# OpenMV-2L.net
KiCad netlist of a schematic drawn in EAGLE
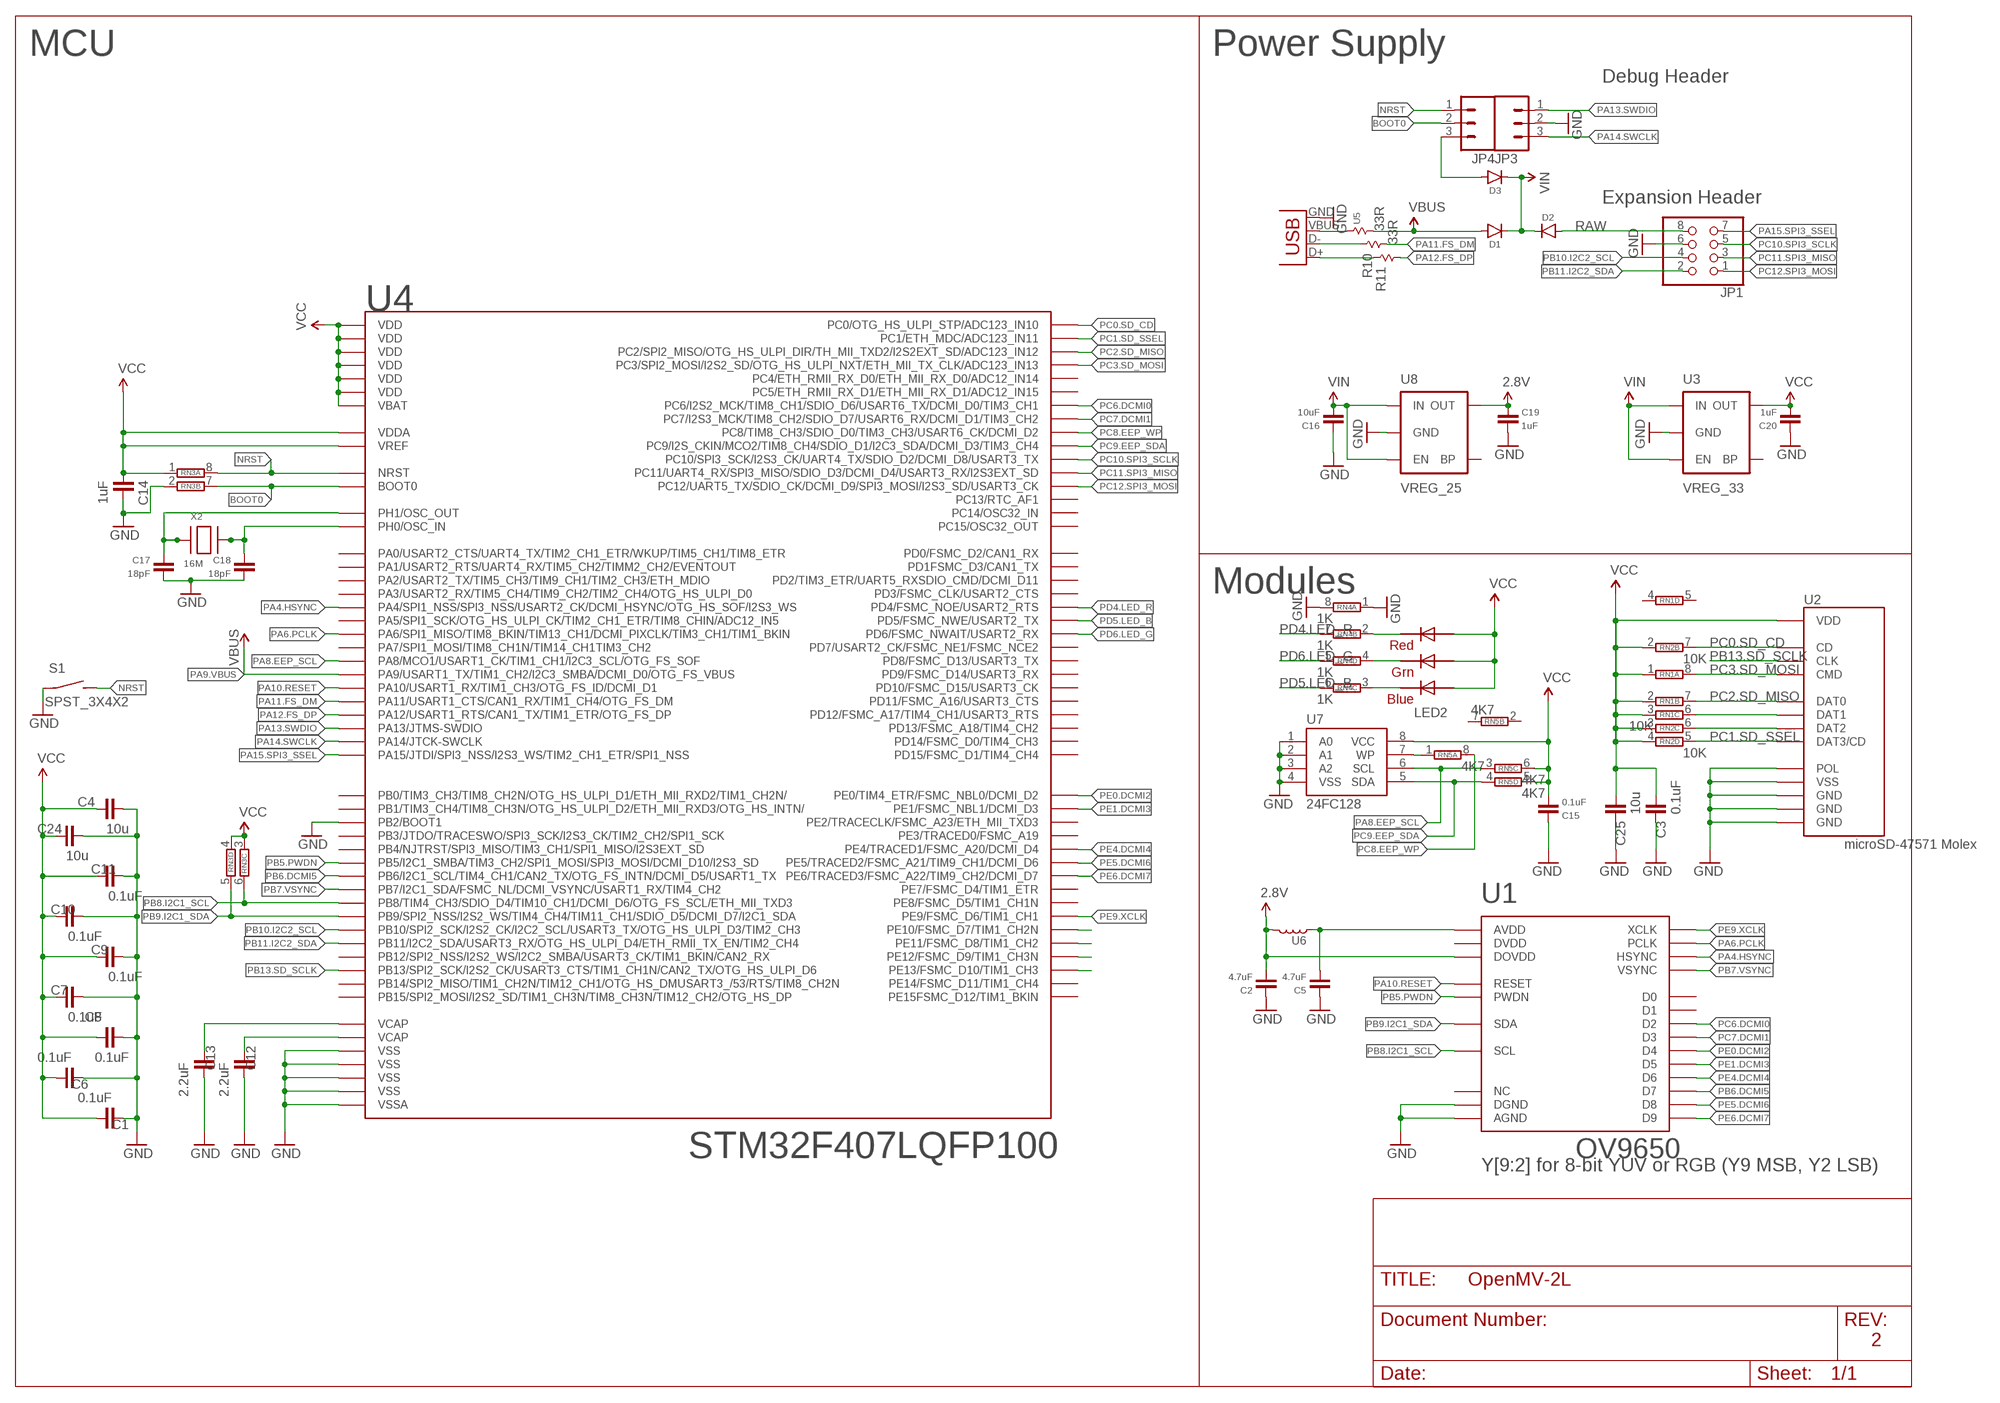
[diagram p0: schematic, sheet 1]

(export (version "E")
  (design (tool "Eeschema 10.0.6"))
  (components
    (comp (ref "C1")
      (value "0.1uF")
      (footprint "eagle-import:0402")
      (libsource (lib "eagle-import") (part "CAP-0402"))
    )
    (comp (ref "C2")
      (value "4.7uF")
      (footprint "eagle-import:0603")
      (libsource (lib "eagle-import") (part "CAP-0603"))
    )
    (comp (ref "C3")
      (value "0.1uF")
      (footprint "eagle-import:0402")
      (libsource (lib "eagle-import") (part "CAP-0402"))
    )
    (comp (ref "C4")
      (value "10u")
      (footprint "eagle-import:0805")
      (libsource (lib "eagle-import") (part "CAP-0805"))
    )
    (comp (ref "C5")
      (value "4.7uF")
      (footprint "eagle-import:0603")
      (libsource (lib "eagle-import") (part "CAP-0603"))
    )
    (comp (ref "C6")
      (value "0.1uF")
      (footprint "eagle-import:0402")
      (libsource (lib "eagle-import") (part "CAP-0402"))
    )
    (comp (ref "C7")
      (value "0.1uF")
      (footprint "eagle-import:0402")
      (libsource (lib "eagle-import") (part "CAP-0402"))
    )
    (comp (ref "C8")
      (value "0.1uF")
      (footprint "eagle-import:0402")
      (libsource (lib "eagle-import") (part "CAP-0402"))
    )
    (comp (ref "C9")
      (value "0.1uF")
      (footprint "eagle-import:0402")
      (libsource (lib "eagle-import") (part "CAP-0402"))
    )
    (comp (ref "C10")
      (value "0.1uF")
      (footprint "eagle-import:0402")
      (libsource (lib "eagle-import") (part "CAP-0402"))
    )
    (comp (ref "C11")
      (value "0.1uF")
      (footprint "eagle-import:0402")
      (libsource (lib "eagle-import") (part "CAP-0402"))
    )
    (comp (ref "C12")
      (value "2.2uF")
      (footprint "eagle-import:0402")
      (libsource (lib "eagle-import") (part "CAP-0402"))
    )
    (comp (ref "C13")
      (value "2.2uF")
      (footprint "eagle-import:0402")
      (libsource (lib "eagle-import") (part "CAP-0402"))
    )
    (comp (ref "C14")
      (value "1uF")
      (footprint "eagle-import:0402")
      (libsource (lib "eagle-import") (part "CAP-0402"))
    )
    (comp (ref "C15")
      (value "0.1uF")
      (footprint "eagle-import:0603")
      (libsource (lib "eagle-import") (part "CAP-0603"))
    )
    (comp (ref "C16")
      (value "10uF")
      (footprint "eagle-import:0805")
      (libsource (lib "eagle-import") (part "CAP-0805"))
    )
    (comp (ref "C17")
      (value "18pF")
      (footprint "eagle-import:0402")
      (libsource (lib "eagle-import") (part "CAP-0402"))
    )
    (comp (ref "C18")
      (value "18pF")
      (footprint "eagle-import:0402")
      (libsource (lib "eagle-import") (part "CAP-0402"))
    )
    (comp (ref "C19")
      (value "1uF")
      (footprint "eagle-import:0603")
      (libsource (lib "eagle-import") (part "CAP-0603"))
    )
    (comp (ref "C20")
      (value "1uF")
      (footprint "eagle-import:0603")
      (libsource (lib "eagle-import") (part "CAP-0603"))
    )
    (comp (ref "C24")
      (value "10u")
      (footprint "eagle-import:0805")
      (libsource (lib "eagle-import") (part "CAP-0805"))
    )
    (comp (ref "C25")
      (value "10u")
      (footprint "eagle-import:0805")
      (libsource (lib "eagle-import") (part "CAP-0805"))
    )
    (comp (ref "D1")
      (value "DIODE-SOD-323")
      (footprint "eagle-import:SOD-323")
      (libsource (lib "eagle-import") (part "DIODE-SOD-323"))
    )
    (comp (ref "D2")
      (value "DIODE-SOD-323")
      (footprint "eagle-import:SOD-323")
      (libsource (lib "eagle-import") (part "DIODE-SOD-323"))
    )
    (comp (ref "D3")
      (value "DIODE-SOD-323")
      (footprint "eagle-import:SOD-323")
      (libsource (lib "eagle-import") (part "DIODE-SOD-323"))
    )
    (comp (ref "JP1")
      (value "PINHD-2X4")
      (footprint "eagle-import:2X04")
      (libsource (lib "eagle-import") (part "PINHD-2X4"))
    )
    (comp (ref "JP3")
      (value "M03PTH")
      (footprint "eagle-import:1X03")
      (libsource (lib "eagle-import") (part "M03PTH"))
    )
    (comp (ref "JP4")
      (value "M03PTH")
      (footprint "eagle-import:1X03")
      (libsource (lib "eagle-import") (part "M03PTH"))
    )
    (comp (ref "LED2")
      (value "RGBLED5050")
      (footprint "eagle-import:RGBLED5050")
      (libsource (lib "eagle-import") (part "RGBLED5050"))
    )
    (comp (ref "R10")
      (value "33R")
      (footprint "eagle-import:0402")
      (libsource (lib "eagle-import") (part "RESISTOR-0402"))
    )
    (comp (ref "R11")
      (value "33R")
      (footprint "eagle-import:0402")
      (libsource (lib "eagle-import") (part "RESISTOR-0402"))
    )
    (comp (ref "RN1")
      (value "4R-NCAT16")
      (footprint "eagle-import:CAT16")
      (fields (field (name "OC_FARNELL") "unknown") (field (name "OC_NEWARK") "unknown"))
      (libsource (lib "eagle-import") (part "4R-NCAT16"))
    )
    (comp (ref "RN2")
      (value "10K")
      (footprint "eagle-import:CAT16")
      (fields (field (name "OC_FARNELL") "unknown") (field (name "OC_NEWARK") "unknown"))
      (libsource (lib "eagle-import") (part "4R-NCAT16"))
    )
    (comp (ref "RN3")
      (value "4R-NCAT16")
      (footprint "eagle-import:CAT16")
      (libsource (lib "eagle-import") (part "4R-NCAT16"))
    )
    (comp (ref "RN4")
      (value "1K")
      (footprint "eagle-import:CAT16")
      (fields (field (name "OC_FARNELL") "unknown") (field (name "OC_NEWARK") "unknown"))
      (libsource (lib "eagle-import") (part "4R-NCAT16"))
    )
    (comp (ref "RN5")
      (value "4K7")
      (footprint "eagle-import:CAT16")
      (fields (field (name "OC_FARNELL") "unknown") (field (name "OC_NEWARK") "unknown"))
      (libsource (lib "eagle-import") (part "4R-NCAT16"))
    )
    (comp (ref "S1")
      (value "SPST_3X4X2")
      (footprint "eagle-import:3X4X2TACT")
      (libsource (lib "eagle-import") (part "SPST_3X4X2"))
    )
    (comp (ref "U1")
      (value "OV9650")
      (footprint "eagle-import:OV9650")
      (libsource (lib "eagle-import") (part "OV9650"))
    )
    (comp (ref "U2")
      (value "microSD-47571 Molex")
      (footprint "eagle-import:USD-47571")
      (libsource (lib "eagle-import") (part "USD-47571"))
    )
    (comp (ref "U3")
      (value "VREG_33")
      (footprint "eagle-import:SOT23-5")
      (libsource (lib "eagle-import") (part "V_REG_LDOSMD"))
    )
    (comp (ref "U4")
      (value "STM32F407LQFP100")
      (footprint "eagle-import:LQFP100")
      (libsource (lib "eagle-import") (part "STM32F407LQFP100"))
    )
    (comp (ref "U5")
      (value "RESISTOR-0402")
      (footprint "eagle-import:0402")
      (libsource (lib "eagle-import") (part "RESISTOR-0402"))
    )
    (comp (ref "U6")
      (value "INDUCTOR-0603")
      (footprint "eagle-import:0603")
      (libsource (lib "eagle-import") (part "INDUCTOR-0603"))
    )
    (comp (ref "U7")
      (value "24FC128")
      (footprint "eagle-import:MSOP8")
      (libsource (lib "eagle-import") (part "24FC128"))
    )
    (comp (ref "U8")
      (value "VREG_25")
      (footprint "eagle-import:SOT23-5")
      (libsource (lib "eagle-import") (part "V_REG_LDOSMD"))
    )
    (comp (ref "X1")
      (value "USB-MICROB")
      (footprint "eagle-import:USB-MICROB")
      (libsource (lib "eagle-import") (part "USB-MICROB"))
    )
    (comp (ref "X2")
      (value "16M")
      (footprint "eagle-import:NX5032")
      (libsource (lib "eagle-import") (part "XTALNX5032"))
    )
  )
  (nets
    (net (code "1") (name "/RAW") (class "Default")
      (node (ref "D2") (pin "2") (pinfunction "A_2") (pintype "passive"))
      (node (ref "JP1") (pin "8") (pinfunction "8_8") (pintype "passive"))
    )
    (net (code "2") (name "2.8V") (class "Default")
      (node (ref "C19") (pin "2") (pinfunction "2_2") (pintype "passive"))
      (node (ref "C2") (pin "1") (pinfunction "1_1") (pintype "passive"))
      (node (ref "U1") (pin "P$11") (pinfunction "DOVDD_P$11") (pintype "bidirectional"))
      (node (ref "U6") (pin "2") (pinfunction "2_2") (pintype "passive"))
      (node (ref "U8") (pin "5") (pinfunction "OUT_5") (pintype "passive"))
    )
    (net (code "3") (name "BOOT0") (class "Default")
      (node (ref "JP4") (pin "2") (pinfunction "2_2") (pintype "passive"))
      (node (ref "RN3") (pin "7") (pinfunction "2_7") (pintype "passive"))
      (node (ref "U4") (pin "94") (pinfunction "BOOT0_94") (pintype "bidirectional"))
    )
    (net (code "4") (name "GND") (class "Default")
      (node (ref "C1") (pin "1") (pinfunction "1_1") (pintype "passive"))
      (node (ref "C10") (pin "2") (pinfunction "2_2") (pintype "passive"))
      (node (ref "C11") (pin "2") (pinfunction "2_2") (pintype "passive"))
      (node (ref "C12") (pin "2") (pinfunction "2_2") (pintype "passive"))
      (node (ref "C13") (pin "2") (pinfunction "2_2") (pintype "passive"))
      (node (ref "C14") (pin "1") (pinfunction "1_1") (pintype "passive"))
      (node (ref "C15") (pin "2") (pinfunction "2_2") (pintype "passive"))
      (node (ref "C16") (pin "2") (pinfunction "2_2") (pintype "passive"))
      (node (ref "C17") (pin "1") (pinfunction "1_1") (pintype "passive"))
      (node (ref "C18") (pin "1") (pinfunction "1_1") (pintype "passive"))
      (node (ref "C19") (pin "1") (pinfunction "1_1") (pintype "passive"))
      (node (ref "C2") (pin "2") (pinfunction "2_2") (pintype "passive"))
      (node (ref "C20") (pin "2") (pinfunction "2_2") (pintype "passive"))
      (node (ref "C24") (pin "1") (pinfunction "1_1") (pintype "passive"))
      (node (ref "C25") (pin "2") (pinfunction "2_2") (pintype "passive"))
      (node (ref "C3") (pin "2") (pinfunction "2_2") (pintype "passive"))
      (node (ref "C4") (pin "1") (pinfunction "1_1") (pintype "passive"))
      (node (ref "C5") (pin "2") (pinfunction "2_2") (pintype "passive"))
      (node (ref "C6") (pin "1") (pinfunction "1_1") (pintype "passive"))
      (node (ref "C7") (pin "2") (pinfunction "2_2") (pintype "passive"))
      (node (ref "C8") (pin "1") (pinfunction "1_1") (pintype "passive"))
      (node (ref "C9") (pin "2") (pinfunction "2_2") (pintype "passive"))
      (node (ref "JP1") (pin "6") (pinfunction "6_6") (pintype "passive"))
      (node (ref "JP3") (pin "2") (pinfunction "2_2") (pintype "passive"))
      (node (ref "RN3") (pin "2") (pinfunction "1_2") (pintype "passive"))
      (node (ref "RN4") (pin "1") (pinfunction "1_1") (pintype "passive"))
      (node (ref "RN4") (pin "8") (pinfunction "2_8") (pintype "passive"))
      (node (ref "S1") (pin "P$1") (pinfunction "P_P$1") (pintype "passive"))
      (node (ref "U1") (pin "P$15") (pinfunction "DGND_P$15") (pintype "bidirectional"))
      (node (ref "U1") (pin "P$2") (pinfunction "AGND_P$2") (pintype "power_in"))
      (node (ref "U2") (pin "G$1") (pinfunction "GND_G$1") (pintype "power_in"))
      (node (ref "U2") (pin "G$2") (pinfunction "GND_G$2") (pintype "power_in"))
      (node (ref "U2") (pin "G$3") (pinfunction "GND_G$3") (pintype "power_in"))
      (node (ref "U2") (pin "G$4") (pinfunction "POL_G$4") (pintype "power_in"))
      (node (ref "U2") (pin "P$6") (pinfunction "VSS_P$6") (pintype "power_in"))
      (node (ref "U3") (pin "2") (pinfunction "GND_2") (pintype "input"))
      (node (ref "U4") (pin "10") (pinfunction "VSS_10") (pintype "power_in"))
      (node (ref "U4") (pin "20") (pinfunction "VSSA_20") (pintype "power_in"))
      (node (ref "U4") (pin "27") (pinfunction "VSS_27") (pintype "power_in"))
      (node (ref "U4") (pin "37") (pinfunction "PB2/BOOT1_37") (pintype "bidirectional"))
      (node (ref "U4") (pin "74") (pinfunction "VSS_74") (pintype "power_in"))
      (node (ref "U4") (pin "99") (pinfunction "VSS_99") (pintype "power_in"))
      (node (ref "U7") (pin "1") (pinfunction "A0_1") (pintype "bidirectional"))
      (node (ref "U7") (pin "2") (pinfunction "A1_2") (pintype "bidirectional"))
      (node (ref "U7") (pin "3") (pinfunction "A2_3") (pintype "bidirectional"))
      (node (ref "U7") (pin "4") (pinfunction "VSS_4") (pintype "power_in"))
      (node (ref "U8") (pin "2") (pinfunction "GND_2") (pintype "input"))
      (node (ref "X1") (pin "GND") (pinfunction "GND_GND") (pintype "bidirectional"))
    )
    (net (code "5") (name "NRST") (class "Default")
      (node (ref "JP4") (pin "1") (pinfunction "1_1") (pintype "passive"))
      (node (ref "RN3") (pin "8") (pinfunction "2_8") (pintype "passive"))
      (node (ref "S1") (pin "P$2") (pinfunction "S_P$2") (pintype "passive"))
      (node (ref "U4") (pin "14") (pinfunction "NRST_14") (pintype "bidirectional"))
    )
    (net (code "6") (name "Net-(C12-Pad1)") (class "Default")
      (node (ref "C12") (pin "1") (pinfunction "1_1") (pintype "passive"))
      (node (ref "U4") (pin "73") (pinfunction "VCAP_73") (pintype "power_in"))
    )
    (net (code "7") (name "Net-(C13-Pad1)") (class "Default")
      (node (ref "C13") (pin "1") (pinfunction "1_1") (pintype "passive"))
      (node (ref "U4") (pin "49") (pinfunction "VCAP_49") (pintype "power_in"))
    )
    (net (code "8") (name "Net-(D3-A)") (class "Default")
      (node (ref "D3") (pin "2") (pinfunction "A_2") (pintype "passive"))
      (node (ref "JP4") (pin "3") (pinfunction "3_3") (pintype "passive"))
    )
    (net (code "9") (name "Net-(LED2-BLUE_C)") (class "Default")
      (node (ref "LED2") (pin "4") (pinfunction "BLUE_C_4") (pintype "bidirectional"))
      (node (ref "RN4") (pin "3") (pinfunction "1_3") (pintype "passive"))
    )
    (net (code "10") (name "Net-(LED2-GREEN_C)") (class "Default")
      (node (ref "LED2") (pin "6") (pinfunction "GREEN_C_6") (pintype "bidirectional"))
      (node (ref "RN4") (pin "4") (pinfunction "1_4") (pintype "passive"))
    )
    (net (code "11") (name "Net-(LED2-RED_C)") (class "Default")
      (node (ref "LED2") (pin "5") (pinfunction "RED_C_5") (pintype "bidirectional"))
      (node (ref "RN4") (pin "2") (pinfunction "1_2") (pintype "passive"))
    )
    (net (code "12") (name "Net-(R10-Pad1)") (class "Default")
      (node (ref "R10") (pin "1") (pinfunction "1_1") (pintype "passive"))
      (node (ref "X1") (pin "D-") (pinfunction "D-_D-") (pintype "bidirectional"))
    )
    (net (code "13") (name "Net-(R11-Pad1)") (class "Default")
      (node (ref "R11") (pin "1") (pinfunction "1_1") (pintype "passive"))
      (node (ref "X1") (pin "D+") (pinfunction "D+_D+") (pintype "bidirectional"))
    )
    (net (code "14") (name "Net-(RN1C-2)") (class "Default")
      (node (ref "RN1") (pin "6") (pinfunction "2_6") (pintype "passive"))
      (node (ref "U2") (pin "P$8") (pinfunction "DAT1_P$8") (pintype "bidirectional"))
    )
    (net (code "15") (name "Net-(RN2C-2)") (class "Default")
      (node (ref "RN2") (pin "6") (pinfunction "2_6") (pintype "passive"))
      (node (ref "U2") (pin "P$1") (pinfunction "DAT2_P$1") (pintype "bidirectional"))
    )
    (net (code "16") (name "Net-(U1-AVDD)") (class "Default")
      (node (ref "C5") (pin "1") (pinfunction "1_1") (pintype "passive"))
      (node (ref "U1") (pin "P$4") (pinfunction "AVDD_P$4") (pintype "power_in"))
      (node (ref "U6") (pin "1") (pinfunction "1_1") (pintype "passive"))
    )
    (net (code "17") (name "Net-(U4-PH0{slash}OSC_IN)") (class "Default")
      (node (ref "C18") (pin "2") (pinfunction "2_2") (pintype "passive"))
      (node (ref "U4") (pin "12") (pinfunction "PH0/OSC_IN_12") (pintype "bidirectional"))
      (node (ref "X2") (pin "P$2") (pinfunction "P$2_P$2") (pintype "bidirectional"))
    )
    (net (code "18") (name "Net-(U4-PH1{slash}OSC_OUT)") (class "Default")
      (node (ref "C17") (pin "2") (pinfunction "2_2") (pintype "passive"))
      (node (ref "U4") (pin "13") (pinfunction "PH1/OSC_OUT_13") (pintype "bidirectional"))
      (node (ref "X2") (pin "P$1") (pinfunction "P$1_P$1") (pintype "bidirectional"))
    )
    (net (code "19") (name "Net-(U5-Pad1)") (class "Default")
      (node (ref "U5") (pin "1") (pinfunction "1_1") (pintype "passive"))
      (node (ref "X1") (pin "VBUS") (pinfunction "VBUS_VBUS") (pintype "bidirectional"))
    )
    (net (code "20") (name "Net-(U7-WP)") (class "Default")
      (node (ref "RN5") (pin "1") (pinfunction "1_1") (pintype "passive"))
      (node (ref "U7") (pin "7") (pinfunction "WP_7") (pintype "bidirectional"))
    )
    (net (code "21") (name "PA4.HSYNC") (class "Default")
      (node (ref "U1") (pin "P$9") (pinfunction "HSYNC_P$9") (pintype "bidirectional"))
      (node (ref "U4") (pin "29") (pinfunction "PA4/SPI1_NSS/SPI3_NSS/USART2_CK/DCMI_HSYNC/OTG_HS_SOF/I2S3_WS_29") (pintype "bidirectional"))
    )
    (net (code "22") (name "PA6.PCLK") (class "Default")
      (node (ref "U1") (pin "P$17") (pinfunction "PCLK_P$17") (pintype "bidirectional"))
      (node (ref "U4") (pin "31") (pinfunction "PA6/SPI1_MISO/TIM8_BKIN/TIM13_CH1/DCMI_PIXCLK/TIM3_CH1/TIM1_BKIN_31") (pintype "bidirectional"))
    )
    (net (code "23") (name "PA8.EEP_SCL") (class "Default")
      (node (ref "RN5") (pin "3") (pinfunction "1_3") (pintype "passive"))
      (node (ref "U4") (pin "67") (pinfunction "PA8/MCO1/USART1_CK/TIM1_CH1/I2C3_SCL/OTG_FS_SOF_67") (pintype "bidirectional"))
      (node (ref "U7") (pin "6") (pinfunction "SCL_6") (pintype "bidirectional"))
    )
    (net (code "24") (name "PA9.VBUS") (class "Default")
      (node (ref "D1") (pin "2") (pinfunction "A_2") (pintype "passive"))
      (node (ref "U4") (pin "68") (pinfunction "PA9/USART1_TX/TIM1_CH2/I2C3_SMBA/DCMI_D0/OTG_FS_VBUS_68") (pintype "bidirectional"))
      (node (ref "U5") (pin "2") (pinfunction "2_2") (pintype "passive"))
    )
    (net (code "25") (name "PA10.RESET") (class "Default")
      (node (ref "U1") (pin "P$6") (pinfunction "RESET_P$6") (pintype "bidirectional"))
      (node (ref "U4") (pin "69") (pinfunction "PA10/USART1_RX/TIM1_CH3/OTG_FS_ID/DCMI_D1_69") (pintype "bidirectional"))
    )
    (net (code "26") (name "PA11.FS_DM") (class "Default")
      (node (ref "R10") (pin "2") (pinfunction "2_2") (pintype "passive"))
      (node (ref "U4") (pin "70") (pinfunction "PA11/USART1_CTS/CAN1_RX/TIM1_CH4/OTG_FS_DM_70") (pintype "bidirectional"))
    )
    (net (code "27") (name "PA12.FS_DP") (class "Default")
      (node (ref "R11") (pin "2") (pinfunction "2_2") (pintype "passive"))
      (node (ref "U4") (pin "71") (pinfunction "PA12/USART1_RTS/CAN1_TX/TIM1_ETR/OTG_FS_DP_71") (pintype "bidirectional"))
    )
    (net (code "28") (name "PA13.SWDIO") (class "Default")
      (node (ref "JP3") (pin "1") (pinfunction "1_1") (pintype "passive"))
      (node (ref "U4") (pin "72") (pinfunction "PA13/JTMS-SWDIO_72") (pintype "bidirectional"))
    )
    (net (code "29") (name "PA14.SWCLK") (class "Default")
      (node (ref "JP3") (pin "3") (pinfunction "3_3") (pintype "passive"))
      (node (ref "U4") (pin "76") (pinfunction "PA14/JTCK-SWCLK_76") (pintype "bidirectional"))
    )
    (net (code "30") (name "PA15.SPI3_SSEL") (class "Default")
      (node (ref "JP1") (pin "7") (pinfunction "7_7") (pintype "passive"))
      (node (ref "U4") (pin "77") (pinfunction "PA15/JTDI/SPI3_NSS/I2S3_WS/TIM2_CH1_ETR/SPI1_NSS_77") (pintype "bidirectional"))
    )
    (net (code "31") (name "PB5.PWDN") (class "Default")
      (node (ref "U1") (pin "P$8") (pinfunction "PWDN_P$8") (pintype "bidirectional"))
      (node (ref "U4") (pin "91") (pinfunction "PB5/I2C1_SMBA/TIM3_CH2/SPI1_MOSI/SPI3_MOSI/DCMI_D10/I2S3_SD_91") (pintype "bidirectional"))
    )
    (net (code "32") (name "PB6.DCMI5") (class "Default")
      (node (ref "U1") (pin "P$16") (pinfunction "D7_P$16") (pintype "bidirectional"))
      (node (ref "U4") (pin "92") (pinfunction "PB6/I2C1_SCL/TIM4_CH1/CAN2_TX/OTG_FS_INTN/DCMI_D5/USART1_TX_92") (pintype "bidirectional"))
    )
    (net (code "33") (name "PB7.VSYNC") (class "Default")
      (node (ref "U1") (pin "P$7") (pinfunction "VSYNC_P$7") (pintype "bidirectional"))
      (node (ref "U4") (pin "93") (pinfunction "PB7/I2C1_SDA/FSMC_NL/DCMI_VSYNC/USART1_RX/TIM4_CH2_93") (pintype "bidirectional"))
    )
    (net (code "34") (name "PB8.I2C1_SCL") (class "Default")
      (node (ref "RN3") (pin "6") (pinfunction "2_6") (pintype "passive"))
      (node (ref "U1") (pin "P$5") (pinfunction "SCL_P$5") (pintype "bidirectional"))
      (node (ref "U4") (pin "95") (pinfunction "PB8/TIM4_CH3/SDIO_D4/TIM10_CH1/DCMI_D6/OTG_FS_SCL/ETH_MII_TXD3_95") (pintype "bidirectional"))
    )
    (net (code "35") (name "PB9.I2C1_SDA") (class "Default")
      (node (ref "RN3") (pin "5") (pinfunction "2_5") (pintype "passive"))
      (node (ref "U1") (pin "P$3") (pinfunction "SDA_P$3") (pintype "bidirectional"))
      (node (ref "U4") (pin "96") (pinfunction "PB9/SPI2_NSS/I2S2_WS/TIM4_CH4/TIM11_CH1/SDIO_D5/DCMI_D7/I2C1_SDA_96") (pintype "bidirectional"))
    )
    (net (code "36") (name "PB10.I2C2_SCL") (class "Default")
      (node (ref "JP1") (pin "4") (pinfunction "4_4") (pintype "passive"))
      (node (ref "U4") (pin "47") (pinfunction "PB10/SPI2_SCK/I2S2_CK/I2C2_SCL/USART3_TX/OTG_HS_ULPI_D3/TIM2_CH3_47") (pintype "bidirectional"))
    )
    (net (code "37") (name "PB11.I2C2_SDA") (class "Default")
      (node (ref "JP1") (pin "2") (pinfunction "2_2") (pintype "passive"))
      (node (ref "U4") (pin "48") (pinfunction "PB11/I2C2_SDA/USART3_RX/OTG_HS_ULPI_D4/ETH_RMII_TX_EN/TIM2_CH4_48") (pintype "bidirectional"))
    )
    (net (code "38") (name "PB13.SD_SCLK") (class "Default")
      (node (ref "U2") (pin "P$5") (pinfunction "CLK_P$5") (pintype "bidirectional"))
      (node (ref "U4") (pin "52") (pinfunction "PB13/SPI2_SCK/I2S2_CK/USART3_CTS/TIM1_CH1N/CAN2_TX/OTG_HS_ULPI_D6_52") (pintype "bidirectional"))
    )
    (net (code "39") (name "PC0.SD_CD") (class "Default")
      (node (ref "RN2") (pin "7") (pinfunction "2_7") (pintype "passive"))
      (node (ref "U2") (pin "G$5") (pinfunction "CD_G$5") (pintype "power_in"))
      (node (ref "U4") (pin "15") (pinfunction "PC0/OTG_HS_ULPI_STP/ADC123_IN10_15") (pintype "bidirectional"))
    )
    (net (code "40") (name "PC1.SD_SSEL") (class "Default")
      (node (ref "RN2") (pin "5") (pinfunction "2_5") (pintype "passive"))
      (node (ref "U2") (pin "P$2") (pinfunction "DAT3/CD_P$2") (pintype "bidirectional"))
      (node (ref "U4") (pin "16") (pinfunction "PC1/ETH_MDC/ADC123_IN11_16") (pintype "bidirectional"))
    )
    (net (code "41") (name "PC2.SD_MISO") (class "Default")
      (node (ref "RN1") (pin "7") (pinfunction "2_7") (pintype "passive"))
      (node (ref "U2") (pin "P$7") (pinfunction "DAT0_P$7") (pintype "bidirectional"))
      (node (ref "U4") (pin "17") (pinfunction "PC2/SPI2_MISO/OTG_HS_ULPI_DIR/TH_MII_TXD2/I2S2EXT_SD/ADC123_IN12_17") (pintype "bidirectional"))
    )
    (net (code "42") (name "PC3.SD_MOSI") (class "Default")
      (node (ref "RN1") (pin "8") (pinfunction "2_8") (pintype "passive"))
      (node (ref "U2") (pin "P$3") (pinfunction "CMD_P$3") (pintype "bidirectional"))
      (node (ref "U4") (pin "18") (pinfunction "PC3/SPI2_MOSI/I2S2_SD/OTG_HS_ULPI_NXT/ETH_MII_TX_CLK/ADC123_IN13_18") (pintype "bidirectional"))
    )
    (net (code "43") (name "PC6.DCMI0") (class "Default")
      (node (ref "U1") (pin "P$19") (pinfunction "D2_P$19") (pintype "bidirectional"))
      (node (ref "U4") (pin "63") (pinfunction "PC6/I2S2_MCK/TIM8_CH1/SDIO_D6/USART6_TX/DCMI_D0/TIM3_CH1_63") (pintype "bidirectional"))
    )
    (net (code "44") (name "PC7.DCMI1") (class "Default")
      (node (ref "U1") (pin "P$21") (pinfunction "D3_P$21") (pintype "bidirectional"))
      (node (ref "U4") (pin "64") (pinfunction "PC7/I2S3_MCK/TIM8_CH2/SDIO_D7/USART6_RX/DCMI_D1/TIM3_CH2_64") (pintype "bidirectional"))
    )
    (net (code "45") (name "PC8.EEP_WP") (class "Default")
      (node (ref "RN5") (pin "8") (pinfunction "2_8") (pintype "passive"))
      (node (ref "U4") (pin "65") (pinfunction "PC8/TIM8_CH3/SDIO_D0/TIM3_CH3/USART6_CK/DCMI_D2_65") (pintype "bidirectional"))
    )
    (net (code "46") (name "PC9.EEP_SDA") (class "Default")
      (node (ref "RN5") (pin "4") (pinfunction "1_4") (pintype "passive"))
      (node (ref "U4") (pin "66") (pinfunction "PC9/I2S_CKIN/MCO2/TIM8_CH4/SDIO_D1/I2C3_SDA/DCMI_D3/TIM3_CH4_66") (pintype "bidirectional"))
      (node (ref "U7") (pin "5") (pinfunction "SDA_5") (pintype "bidirectional"))
    )
    (net (code "47") (name "PC10.SPI3_SCLK") (class "Default")
      (node (ref "JP1") (pin "5") (pinfunction "5_5") (pintype "passive"))
      (node (ref "U4") (pin "78") (pinfunction "PC10/SPI3_SCK/I2S3_CK/UART4_TX/SDIO_D2/DCMI_D8/USART3_TX_78") (pintype "bidirectional"))
    )
    (net (code "48") (name "PC11.SPI3_MISO") (class "Default")
      (node (ref "JP1") (pin "3") (pinfunction "3_3") (pintype "passive"))
      (node (ref "U4") (pin "79") (pinfunction "PC11/UART4_RX/SPI3_MISO/SDIO_D3/DCMI_D4/USART3_RX/I2S3EXT_SD_79") (pintype "bidirectional"))
    )
    (net (code "49") (name "PC12.SPI3_MOSI") (class "Default")
      (node (ref "JP1") (pin "1") (pinfunction "1_1") (pintype "passive"))
      (node (ref "U4") (pin "80") (pinfunction "PC12/UART5_TX/SDIO_CK/DCMI_D9/SPI3_MOSI/I2S3_SD/USART3_CK_80") (pintype "bidirectional"))
    )
    (net (code "50") (name "PD4.LED_R") (class "Default")
      (node (ref "RN4") (pin "7") (pinfunction "2_7") (pintype "passive"))
      (node (ref "U4") (pin "85") (pinfunction "PD4/FSMC_NOE/USART2_RTS_85") (pintype "bidirectional"))
    )
    (net (code "51") (name "PD5.LED_B") (class "Default")
      (node (ref "RN4") (pin "6") (pinfunction "2_6") (pintype "passive"))
      (node (ref "U4") (pin "86") (pinfunction "PD5/FSMC_NWE/USART2_TX_86") (pintype "bidirectional"))
    )
    (net (code "52") (name "PD6.LED_G") (class "Default")
      (node (ref "RN4") (pin "5") (pinfunction "2_5") (pintype "passive"))
      (node (ref "U4") (pin "87") (pinfunction "PD6/FSMC_NWAIT/USART2_RX_87") (pintype "bidirectional"))
    )
    (net (code "53") (name "PE0.DCMI2") (class "Default")
      (node (ref "U1") (pin "P$22") (pinfunction "D4_P$22") (pintype "bidirectional"))
      (node (ref "U4") (pin "97") (pinfunction "PE0/TIM4_ETR/FSMC_NBL0/DCMI_D2_97") (pintype "bidirectional"))
    )
    (net (code "54") (name "PE1.DCMI3") (class "Default")
      (node (ref "U1") (pin "P$20") (pinfunction "D5_P$20") (pintype "bidirectional"))
      (node (ref "U4") (pin "98") (pinfunction "PE1/FSMC_NBL1/DCMI_D3_98") (pintype "bidirectional"))
    )
    (net (code "55") (name "PE4.DCMI4") (class "Default")
      (node (ref "U1") (pin "P$18") (pinfunction "D6_P$18") (pintype "bidirectional"))
      (node (ref "U4") (pin "3") (pinfunction "PE4/TRACED1/FSMC_A20/DCMI_D4_3") (pintype "bidirectional"))
    )
    (net (code "56") (name "PE5.DCMI6") (class "Default")
      (node (ref "U1") (pin "P$14") (pinfunction "D8_P$14") (pintype "bidirectional"))
      (node (ref "U4") (pin "4") (pinfunction "PE5/TRACED2/FSMC_A21/TIM9_CH1/DCMI_D6_4") (pintype "bidirectional"))
    )
    (net (code "57") (name "PE6.DCMI7") (class "Default")
      (node (ref "U1") (pin "P$12") (pinfunction "D9_P$12") (pintype "bidirectional"))
      (node (ref "U4") (pin "5") (pinfunction "PE6/TRACED3/FSMC_A22/TIM9_CH2/DCMI_D7_5") (pintype "bidirectional"))
    )
    (net (code "58") (name "PE9.XCLK") (class "Default")
      (node (ref "U1") (pin "P$13") (pinfunction "XCLK_P$13") (pintype "bidirectional"))
      (node (ref "U4") (pin "40") (pinfunction "PE9/FSMC_D6/TIM1_CH1_40") (pintype "bidirectional"))
    )
    (net (code "59") (name "VCC") (class "Default")
      (node (ref "C1") (pin "2") (pinfunction "2_2") (pintype "passive"))
      (node (ref "C10") (pin "1") (pinfunction "1_1") (pintype "passive"))
      (node (ref "C11") (pin "1") (pinfunction "1_1") (pintype "passive"))
      (node (ref "C14") (pin "2") (pinfunction "2_2") (pintype "passive"))
      (node (ref "C15") (pin "1") (pinfunction "1_1") (pintype "passive"))
      (node (ref "C20") (pin "1") (pinfunction "1_1") (pintype "passive"))
      (node (ref "C24") (pin "2") (pinfunction "2_2") (pintype "passive"))
      (node (ref "C25") (pin "1") (pinfunction "1_1") (pintype "passive"))
      (node (ref "C3") (pin "1") (pinfunction "1_1") (pintype "passive"))
      (node (ref "C4") (pin "2") (pinfunction "2_2") (pintype "passive"))
      (node (ref "C6") (pin "2") (pinfunction "2_2") (pintype "passive"))
      (node (ref "C7") (pin "1") (pinfunction "1_1") (pintype "passive"))
      (node (ref "C8") (pin "2") (pinfunction "2_2") (pintype "passive"))
      (node (ref "C9") (pin "1") (pinfunction "1_1") (pintype "passive"))
      (node (ref "LED2") (pin "1") (pinfunction "GREEN_A_1") (pintype "bidirectional"))
      (node (ref "LED2") (pin "2") (pinfunction "RED_A_2") (pintype "bidirectional"))
      (node (ref "LED2") (pin "3") (pinfunction "BLUE_A_3") (pintype "bidirectional"))
      (node (ref "RN1") (pin "1") (pinfunction "1_1") (pintype "passive"))
      (node (ref "RN1") (pin "2") (pinfunction "1_2") (pintype "passive"))
      (node (ref "RN1") (pin "3") (pinfunction "1_3") (pintype "passive"))
      (node (ref "RN2") (pin "2") (pinfunction "1_2") (pintype "passive"))
      (node (ref "RN2") (pin "3") (pinfunction "1_3") (pintype "passive"))
      (node (ref "RN2") (pin "4") (pinfunction "1_4") (pintype "passive"))
      (node (ref "RN3") (pin "1") (pinfunction "1_1") (pintype "passive"))
      (node (ref "RN3") (pin "3") (pinfunction "1_3") (pintype "passive"))
      (node (ref "RN3") (pin "4") (pinfunction "1_4") (pintype "passive"))
      (node (ref "RN5") (pin "5") (pinfunction "2_5") (pintype "passive"))
      (node (ref "RN5") (pin "6") (pinfunction "2_6") (pintype "passive"))
      (node (ref "U2") (pin "P$4") (pinfunction "VDD_P$4") (pintype "power_in"))
      (node (ref "U3") (pin "5") (pinfunction "OUT_5") (pintype "passive"))
      (node (ref "U4") (pin "100") (pinfunction "VDD_100") (pintype "power_in"))
      (node (ref "U4") (pin "11") (pinfunction "VDD_11") (pintype "power_in"))
      (node (ref "U4") (pin "19") (pinfunction "VDD_19") (pintype "power_in"))
      (node (ref "U4") (pin "21") (pinfunction "VREF_21") (pintype "power_in"))
      (node (ref "U4") (pin "22") (pinfunction "VDDA_22") (pintype "power_in"))
      (node (ref "U4") (pin "28") (pinfunction "VDD_28") (pintype "power_in"))
      (node (ref "U4") (pin "50") (pinfunction "VDD_50") (pintype "power_in"))
      (node (ref "U4") (pin "6") (pinfunction "VBAT_6") (pintype "power_in"))
      (node (ref "U4") (pin "75") (pinfunction "VDD_75") (pintype "power_in"))
      (node (ref "U7") (pin "8") (pinfunction "VCC_8") (pintype "power_in"))
    )
    (net (code "60") (name "VIN") (class "Default")
      (node (ref "C16") (pin "1") (pinfunction "1_1") (pintype "passive"))
      (node (ref "D1") (pin "1") (pinfunction "C_1") (pintype "passive"))
      (node (ref "D2") (pin "1") (pinfunction "C_1") (pintype "passive"))
      (node (ref "D3") (pin "1") (pinfunction "C_1") (pintype "passive"))
      (node (ref "U3") (pin "1") (pinfunction "IN_1") (pintype "input"))
      (node (ref "U3") (pin "3") (pinfunction "EN_3") (pintype "input"))
      (node (ref "U8") (pin "1") (pinfunction "IN_1") (pintype "input"))
      (node (ref "U8") (pin "3") (pinfunction "EN_3") (pintype "input"))
    )
    (net (code "61") (name "unconnected-(RN1D-1-Pad4)") (class "Default")
      (node (ref "RN1") (pin "4") (pinfunction "1_4") (pintype "passive"))
    )
    (net (code "62") (name "unconnected-(RN1D-2-Pad5)") (class "Default")
      (node (ref "RN1") (pin "5") (pinfunction "2_5") (pintype "passive"))
    )
    (net (code "63") (name "unconnected-(RN5B-1-Pad2)") (class "Default")
      (node (ref "RN5") (pin "2") (pinfunction "1_2") (pintype "passive"))
    )
    (net (code "64") (name "unconnected-(RN5B-2-Pad7)") (class "Default")
      (node (ref "RN5") (pin "7") (pinfunction "2_7") (pintype "passive"))
    )
    (net (code "65") (name "unconnected-(U1-D0-PadP$24)") (class "Default")
      (node (ref "U1") (pin "P$24") (pinfunction "D0_P$24") (pintype "bidirectional"))
    )
    (net (code "66") (name "unconnected-(U1-D1-PadP$23)") (class "Default")
      (node (ref "U1") (pin "P$23") (pinfunction "D1_P$23") (pintype "bidirectional"))
    )
    (net (code "67") (name "unconnected-(U1-DVDD-PadP$10)") (class "Default")
      (node (ref "U1") (pin "P$10") (pinfunction "DVDD_P$10") (pintype "bidirectional"))
    )
    (net (code "68") (name "unconnected-(U1-NC-PadP$1)") (class "Default")
      (node (ref "U1") (pin "P$1") (pinfunction "NC_P$1") (pintype "no_connect"))
    )
    (net (code "69") (name "unconnected-(U3-BP-Pad4)") (class "Default")
      (node (ref "U3") (pin "4") (pinfunction "BP_4") (pintype "input"))
    )
    (net (code "70") (name "unconnected-(U4-PA0{slash}USART2_CTS{slash}UART4_TX{slash}TIM2_CH1_ETR{slash}WKUP{slash}TIM5_CH1{slash}TIM8_ETR-Pad23)") (class "Default")
      (node (ref "U4") (pin "23") (pinfunction "PA0/USART2_CTS/UART4_TX/TIM2_CH1_ETR/WKUP/TIM5_CH1/TIM8_ETR_23") (pintype "bidirectional"))
    )
    (net (code "71") (name "unconnected-(U4-PA1{slash}USART2_RTS{slash}UART4_RX{slash}TIM5_CH2{slash}TIMM2_CH2{slash}EVENTOUT-Pad24)") (class "Default")
      (node (ref "U4") (pin "24") (pinfunction "PA1/USART2_RTS/UART4_RX/TIM5_CH2/TIMM2_CH2/EVENTOUT_24") (pintype "bidirectional"))
    )
    (net (code "72") (name "unconnected-(U4-PA2{slash}USART2_TX{slash}TIM5_CH3{slash}TIM9_CH1{slash}TIM2_CH3{slash}ETH_MDIO-Pad25)") (class "Default")
      (node (ref "U4") (pin "25") (pinfunction "PA2/USART2_TX/TIM5_CH3/TIM9_CH1/TIM2_CH3/ETH_MDIO_25") (pintype "bidirectional"))
    )
    (net (code "73") (name "unconnected-(U4-PA3{slash}USART2_RX{slash}TIM5_CH4{slash}TIM9_CH2{slash}TIM2_CH4{slash}OTG_HS_ULPI_D0-Pad26)") (class "Default")
      (node (ref "U4") (pin "26") (pinfunction "PA3/USART2_RX/TIM5_CH4/TIM9_CH2/TIM2_CH4/OTG_HS_ULPI_D0_26") (pintype "bidirectional"))
    )
    (net (code "74") (name "unconnected-(U4-PA5{slash}SPI1_SCK{slash}OTG_HS_ULPI_CK{slash}TIM2_CH1_ETR{slash}TIM8_CHIN{slash}ADC12_IN5-Pad30)") (class "Default")
      (node (ref "U4") (pin "30") (pinfunction "PA5/SPI1_SCK/OTG_HS_ULPI_CK/TIM2_CH1_ETR/TIM8_CHIN/ADC12_IN5_30") (pintype "bidirectional"))
    )
    (net (code "75") (name "unconnected-(U4-PA7{slash}SPI1_MOSI{slash}TIM8_CH1N{slash}TIM14_CH1TIM3_CH2-Pad32)") (class "Default")
      (node (ref "U4") (pin "32") (pinfunction "PA7/SPI1_MOSI/TIM8_CH1N/TIM14_CH1TIM3_CH2_32") (pintype "bidirectional"))
    )
    (net (code "76") (name "unconnected-(U4-PB0{slash}TIM3_CH3{slash}TIM8_CH2N{slash}OTG_HS_ULPI_D1{slash}ETH_MII_RXD2{slash}TIM1_CH2N{slash}-Pad35)") (class "Default")
      (node (ref "U4") (pin "35") (pinfunction "PB0/TIM3_CH3/TIM8_CH2N/OTG_HS_ULPI_D1/ETH_MII_RXD2/TIM1_CH2N/_35") (pintype "bidirectional"))
    )
    (net (code "77") (name "unconnected-(U4-PB1{slash}TIM3_CH4{slash}TIM8_CH3N{slash}OTG_HS_ULPI_D2{slash}ETH_MII_RXD3{slash}OTG_HS_INTN{slash}-Pad36)") (class "Default")
      (node (ref "U4") (pin "36") (pinfunction "PB1/TIM3_CH4/TIM8_CH3N/OTG_HS_ULPI_D2/ETH_MII_RXD3/OTG_HS_INTN/_36") (pintype "bidirectional"))
    )
    (net (code "78") (name "unconnected-(U4-PB3{slash}JTDO{slash}TRACESWO{slash}SPI3_SCK{slash}I2S3_CK{slash}TIM2_CH2{slash}SPI1_SCK-Pad89)") (class "Default")
      (node (ref "U4") (pin "89") (pinfunction "PB3/JTDO/TRACESWO/SPI3_SCK/I2S3_CK/TIM2_CH2/SPI1_SCK_89") (pintype "bidirectional"))
    )
    (net (code "79") (name "unconnected-(U4-PB4{slash}NJTRST{slash}SPI3_MISO{slash}TIM3_CH1{slash}SPI1_MISO{slash}I2S3EXT_SD-Pad90)") (class "Default")
      (node (ref "U4") (pin "90") (pinfunction "PB4/NJTRST/SPI3_MISO/TIM3_CH1/SPI1_MISO/I2S3EXT_SD_90") (pintype "bidirectional"))
    )
    (net (code "80") (name "unconnected-(U4-PB12{slash}SPI2_NSS{slash}I2S2_WS{slash}I2C2_SMBA{slash}USART3_CK{slash}TIM1_BKIN{slash}CAN2_RX-Pad51)") (class "Default")
      (node (ref "U4") (pin "51") (pinfunction "PB12/SPI2_NSS/I2S2_WS/I2C2_SMBA/USART3_CK/TIM1_BKIN/CAN2_RX_51") (pintype "bidirectional"))
    )
    (net (code "81") (name "unconnected-(U4-PB14{slash}SPI2_MISO{slash}TIM1_CH2N{slash}TIM12_CH1{slash}OTG_HS_DMUSART3_{slash}53{slash}RTS{slash}TIM8_CH2N-Pad53)") (class "Default")
      (node (ref "U4") (pin "53") (pinfunction "PB14/SPI2_MISO/TIM1_CH2N/TIM12_CH1/OTG_HS_DMUSART3_/53/RTS/TIM8_CH2N_53") (pintype "bidirectional"))
    )
    (net (code "82") (name "unconnected-(U4-PB15{slash}SPI2_MOSI{slash}I2S2_SD{slash}TIM1_CH3N{slash}TIM8_CH3N{slash}TIM12_CH2{slash}OTG_HS_DP-Pad54)") (class "Default")
      (node (ref "U4") (pin "54") (pinfunction "PB15/SPI2_MOSI/I2S2_SD/TIM1_CH3N/TIM8_CH3N/TIM12_CH2/OTG_HS_DP_54") (pintype "bidirectional"))
    )
    (net (code "83") (name "unconnected-(U4-PC4{slash}ETH_RMII_RX_D0{slash}ETH_MII_RX_D0{slash}ADC12_IN14-Pad33)") (class "Default")
      (node (ref "U4") (pin "33") (pinfunction "PC4/ETH_RMII_RX_D0/ETH_MII_RX_D0/ADC12_IN14_33") (pintype "bidirectional"))
    )
    (net (code "84") (name "unconnected-(U4-PC5{slash}ETH_RMII_RX_D1{slash}ETH_MII_RX_D1{slash}ADC12_IN15-Pad34)") (class "Default")
      (node (ref "U4") (pin "34") (pinfunction "PC5/ETH_RMII_RX_D1/ETH_MII_RX_D1/ADC12_IN15_34") (pintype "bidirectional"))
    )
    (net (code "85") (name "unconnected-(U4-PC13{slash}RTC_AF1-Pad7)") (class "Default")
      (node (ref "U4") (pin "7") (pinfunction "PC13/RTC_AF1_7") (pintype "bidirectional"))
    )
    (net (code "86") (name "unconnected-(U4-PC14{slash}OSC32_IN-Pad8)") (class "Default")
      (node (ref "U4") (pin "8") (pinfunction "PC14/OSC32_IN_8") (pintype "bidirectional"))
    )
    (net (code "87") (name "unconnected-(U4-PC15{slash}OSC32_OUT-Pad9)") (class "Default")
      (node (ref "U4") (pin "9") (pinfunction "PC15/OSC32_OUT_9") (pintype "bidirectional"))
    )
    (net (code "88") (name "unconnected-(U4-PD0{slash}FSMC_D2{slash}CAN1_RX-Pad81)") (class "Default")
      (node (ref "U4") (pin "81") (pinfunction "PD0/FSMC_D2/CAN1_RX_81") (pintype "bidirectional"))
    )
    (net (code "89") (name "unconnected-(U4-PD1FSMC_D3{slash}CAN1_TX-Pad82)") (class "Default")
      (node (ref "U4") (pin "82") (pinfunction "PD1FSMC_D3/CAN1_TX_82") (pintype "bidirectional"))
    )
    (net (code "90") (name "unconnected-(U4-PD2{slash}TIM3_ETR{slash}UART5_RXSDIO_CMD{slash}DCMI_D11-Pad83)") (class "Default")
      (node (ref "U4") (pin "83") (pinfunction "PD2/TIM3_ETR/UART5_RXSDIO_CMD/DCMI_D11_83") (pintype "bidirectional"))
    )
    (net (code "91") (name "unconnected-(U4-PD3{slash}FSMC_CLK{slash}USART2_CTS-Pad84)") (class "Default")
      (node (ref "U4") (pin "84") (pinfunction "PD3/FSMC_CLK/USART2_CTS_84") (pintype "bidirectional"))
    )
    (net (code "92") (name "unconnected-(U4-PD7{slash}USART2_CK{slash}FSMC_NE1{slash}FSMC_NCE2-Pad88)") (class "Default")
      (node (ref "U4") (pin "88") (pinfunction "PD7/USART2_CK/FSMC_NE1/FSMC_NCE2_88") (pintype "bidirectional"))
    )
    (net (code "93") (name "unconnected-(U4-PD8{slash}FSMC_D13{slash}USART3_TX-Pad55)") (class "Default")
      (node (ref "U4") (pin "55") (pinfunction "PD8/FSMC_D13/USART3_TX_55") (pintype "bidirectional"))
    )
    (net (code "94") (name "unconnected-(U4-PD9{slash}FSMC_D14{slash}USART3_RX-Pad56)") (class "Default")
      (node (ref "U4") (pin "56") (pinfunction "PD9/FSMC_D14/USART3_RX_56") (pintype "bidirectional"))
    )
    (net (code "95") (name "unconnected-(U4-PD10{slash}FSMC_D15{slash}USART3_CK-Pad57)") (class "Default")
      (node (ref "U4") (pin "57") (pinfunction "PD10/FSMC_D15/USART3_CK_57") (pintype "bidirectional"))
    )
    (net (code "96") (name "unconnected-(U4-PD11{slash}FSMC_A16{slash}USART3_CTS-Pad58)") (class "Default")
      (node (ref "U4") (pin "58") (pinfunction "PD11/FSMC_A16/USART3_CTS_58") (pintype "bidirectional"))
    )
    (net (code "97") (name "unconnected-(U4-PD12{slash}FSMC_A17{slash}TIM4_CH1{slash}USART3_RTS-Pad59)") (class "Default")
      (node (ref "U4") (pin "59") (pinfunction "PD12/FSMC_A17/TIM4_CH1/USART3_RTS_59") (pintype "bidirectional"))
    )
    (net (code "98") (name "unconnected-(U4-PD13{slash}FSMC_A18{slash}TIM4_CH2-Pad60)") (class "Default")
      (node (ref "U4") (pin "60") (pinfunction "PD13/FSMC_A18/TIM4_CH2_60") (pintype "bidirectional"))
    )
    (net (code "99") (name "unconnected-(U4-PD14{slash}FSMC_D0{slash}TIM4_CH3-Pad61)") (class "Default")
      (node (ref "U4") (pin "61") (pinfunction "PD14/FSMC_D0/TIM4_CH3_61") (pintype "bidirectional"))
    )
    (net (code "100") (name "unconnected-(U4-PD15{slash}FSMC_D1{slash}TIM4_CH4-Pad62)") (class "Default")
      (node (ref "U4") (pin "62") (pinfunction "PD15/FSMC_D1/TIM4_CH4_62") (pintype "bidirectional"))
    )
    (net (code "101") (name "unconnected-(U4-PE2{slash}TRACECLK{slash}FSMC_A23{slash}ETH_MII_TXD3-Pad1)") (class "Default")
      (node (ref "U4") (pin "1") (pinfunction "PE2/TRACECLK/FSMC_A23/ETH_MII_TXD3_1") (pintype "bidirectional"))
    )
    (net (code "102") (name "unconnected-(U4-PE3{slash}TRACED0{slash}FSMC_A19-Pad2)") (class "Default")
      (node (ref "U4") (pin "2") (pinfunction "PE3/TRACED0/FSMC_A19_2") (pintype "bidirectional"))
    )
    (net (code "103") (name "unconnected-(U4-PE7{slash}FSMC_D4{slash}TIM1_ETR-Pad38)") (class "Default")
      (node (ref "U4") (pin "38") (pinfunction "PE7/FSMC_D4/TIM1_ETR_38") (pintype "bidirectional"))
    )
    (net (code "104") (name "unconnected-(U4-PE8{slash}FSMC_D5{slash}TIM1_CH1N-Pad39)") (class "Default")
      (node (ref "U4") (pin "39") (pinfunction "PE8/FSMC_D5/TIM1_CH1N_39") (pintype "bidirectional"))
    )
    (net (code "105") (name "unconnected-(U4-PE10{slash}FSMC_D7{slash}TIM1_CH2N-Pad41)") (class "Default")
      (node (ref "U4") (pin "41") (pinfunction "PE10/FSMC_D7/TIM1_CH2N_41") (pintype "bidirectional"))
    )
    (net (code "106") (name "unconnected-(U4-PE11{slash}FSMC_D8{slash}TIM1_CH2-Pad42)") (class "Default")
      (node (ref "U4") (pin "42") (pinfunction "PE11/FSMC_D8/TIM1_CH2_42") (pintype "bidirectional"))
    )
    (net (code "107") (name "unconnected-(U4-PE12{slash}FSMC_D9{slash}TIM1_CH3N-Pad43)") (class "Default")
      (node (ref "U4") (pin "43") (pinfunction "PE12/FSMC_D9/TIM1_CH3N_43") (pintype "bidirectional"))
    )
    (net (code "108") (name "unconnected-(U4-PE13{slash}FSMC_D10{slash}TIM1_CH3-Pad44)") (class "Default")
      (node (ref "U4") (pin "44") (pinfunction "PE13/FSMC_D10/TIM1_CH3_44") (pintype "bidirectional"))
    )
    (net (code "109") (name "unconnected-(U4-PE14{slash}FSMC_D11{slash}TIM1_CH4-Pad45)") (class "Default")
      (node (ref "U4") (pin "45") (pinfunction "PE14/FSMC_D11/TIM1_CH4_45") (pintype "bidirectional"))
    )
    (net (code "110") (name "unconnected-(U4-PE15FSMC_D12{slash}TIM1_BKIN-Pad46)") (class "Default")
      (node (ref "U4") (pin "46") (pinfunction "PE15FSMC_D12/TIM1_BKIN_46") (pintype "bidirectional"))
    )
    (net (code "111") (name "unconnected-(U8-BP-Pad4)") (class "Default")
      (node (ref "U8") (pin "4") (pinfunction "BP_4") (pintype "input"))
    )
  )
)
